# WC_Lower.net
KiCad netlist of a schematic drawn in EAGLE
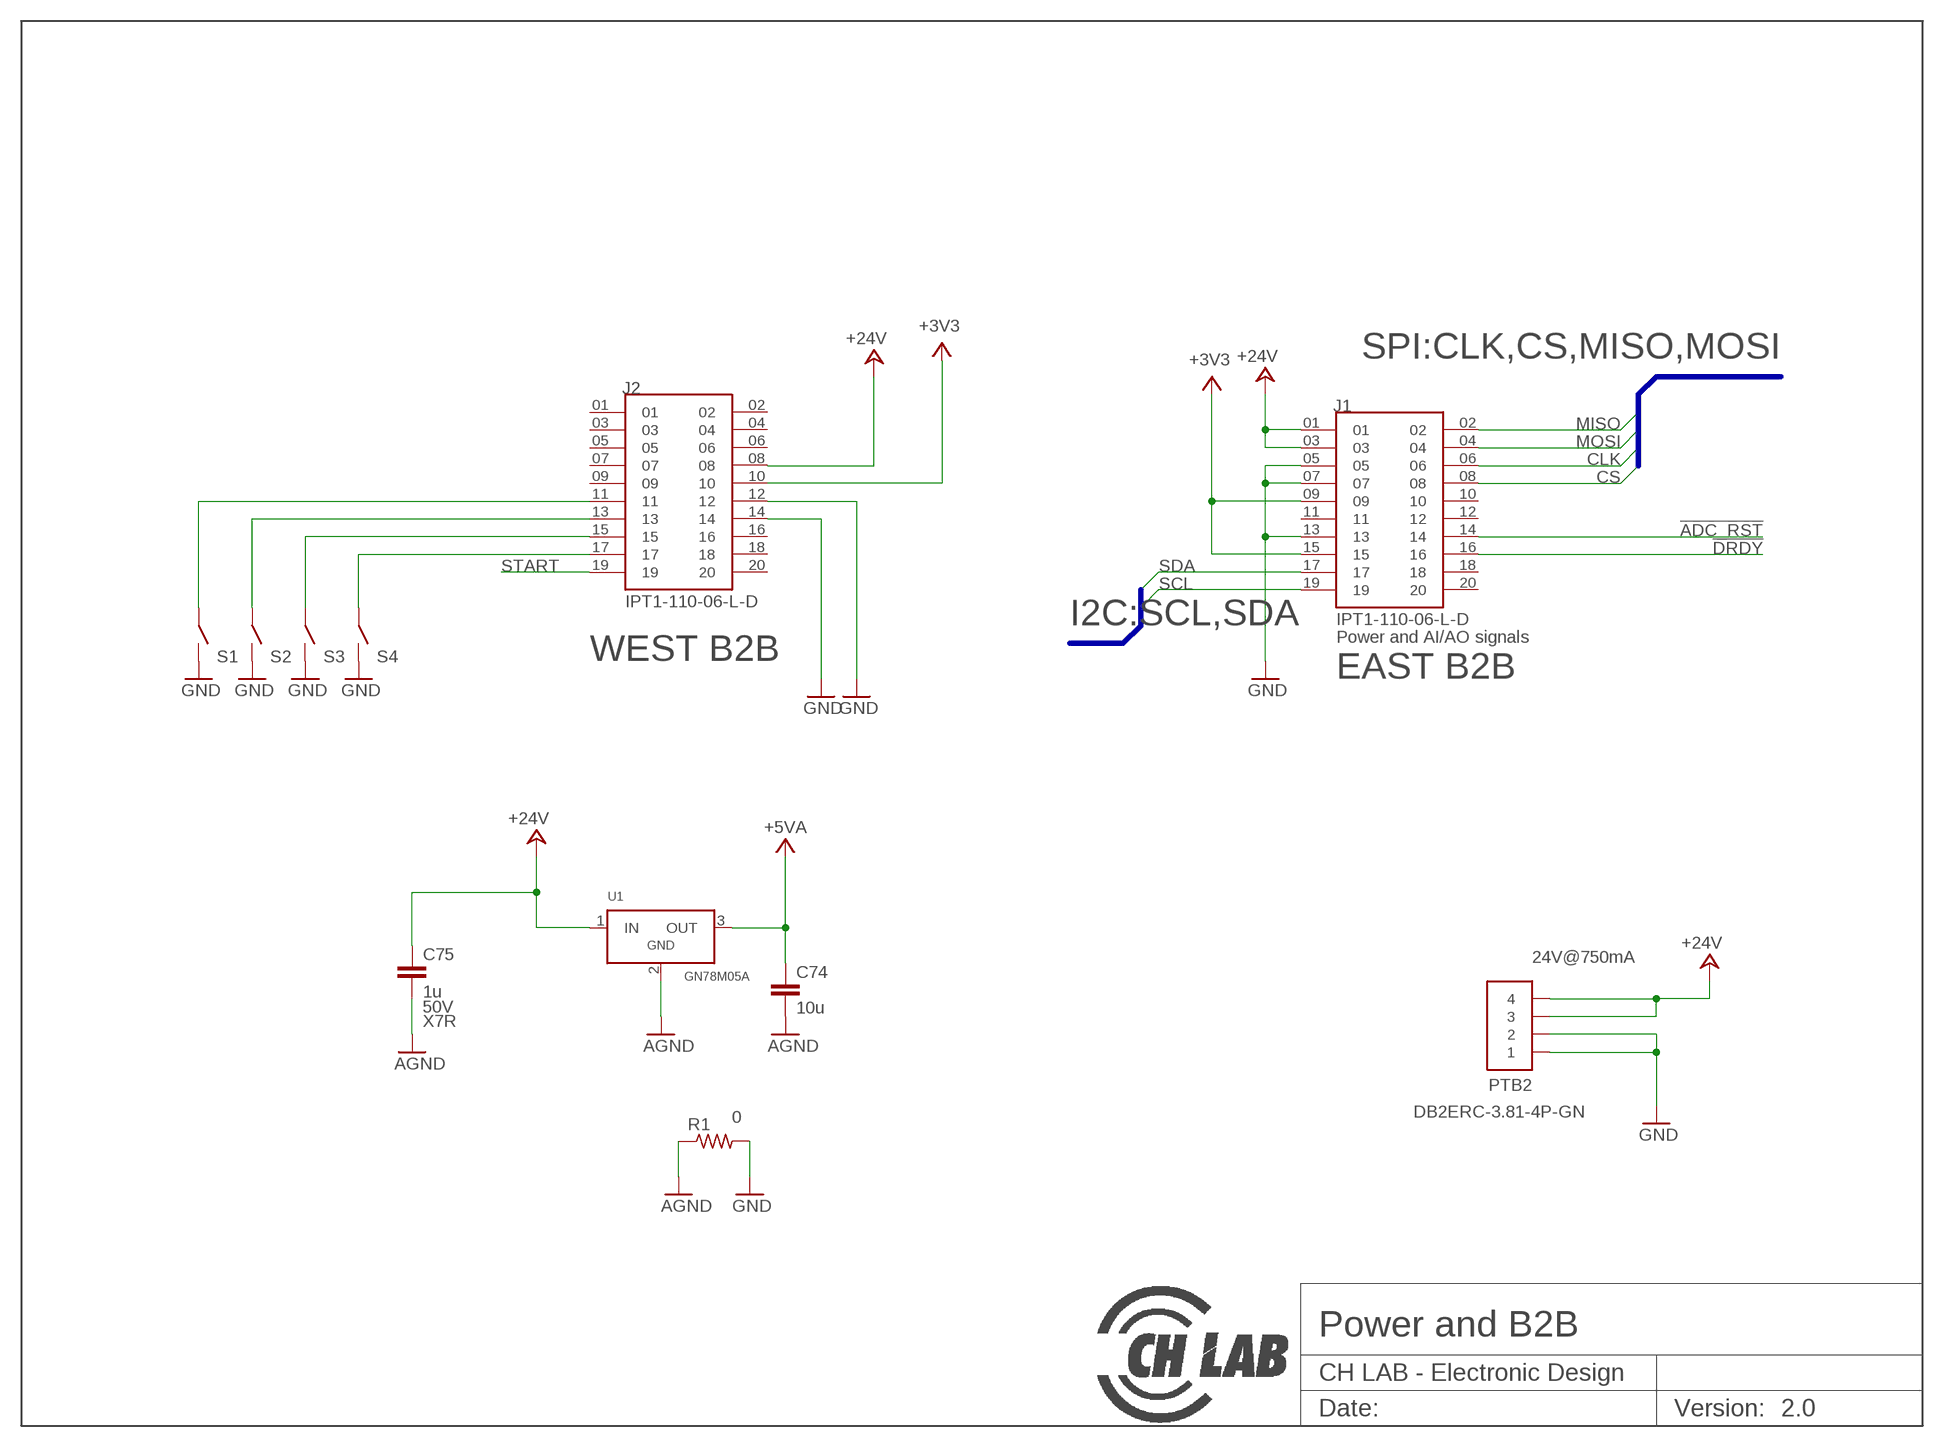
[diagram p0: schematic, sheet 1]
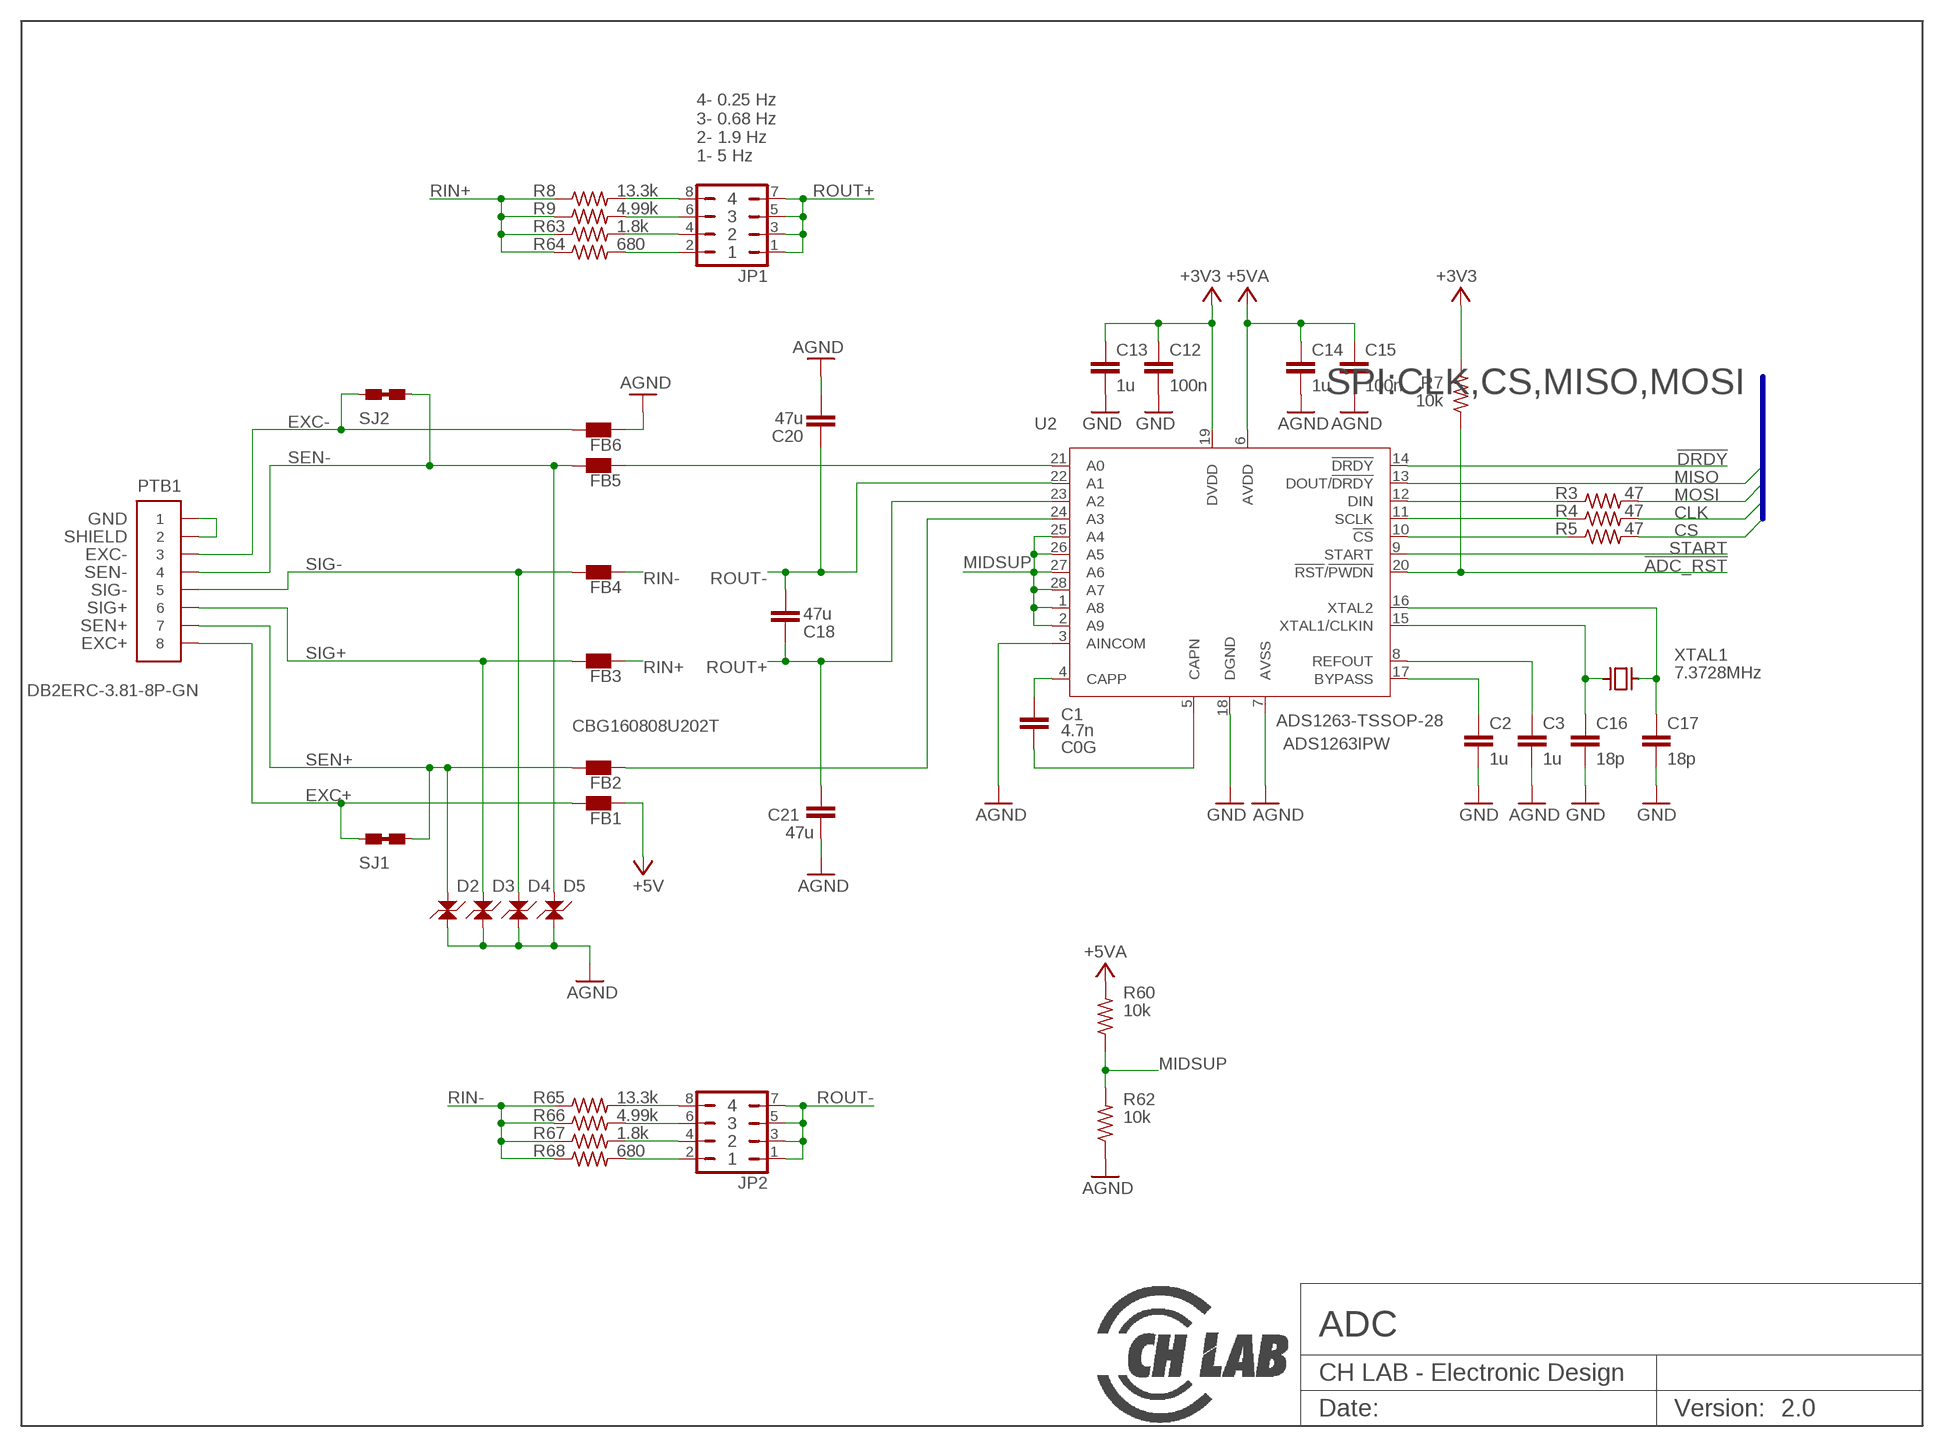
[diagram p1: schematic, sheet 2]

(export (version "E")
  (design (tool "Eeschema 10.0.6"))
  (components
    (comp (ref "C74")
      (value "10u")
      (footprint "eagle-import:C_0805")
      (libsource (lib "eagle-import") (part "C_0805"))
    )
    (comp (ref "C75")
      (value "1u")
      (footprint "eagle-import:C_1206")
      (fields (field (name "D") "X7R") (field (name "ESR") "LOW") (field (name "V") "50V"))
      (libsource (lib "eagle-import") (part "C_1206"))
    )
    (comp (ref "J1")
      (value "IPT1-110-06-L-D")
      (footprint "eagle-import:SAMTEC_IPT1-110-06-L-D")
      (fields (field (name "MANUFACTURER") "Samtec"))
      (libsource (lib "eagle-import") (part "IPT1-110-06-L-D"))
    )
    (comp (ref "J2")
      (value "IPT1-110-06-L-D")
      (footprint "eagle-import:SAMTEC_IPT1-110-06-L-D")
      (fields (field (name "MANUFACTURER") "Samtec"))
      (libsource (lib "eagle-import") (part "IPT1-110-06-L-D"))
    )
    (comp (ref "PTB2")
      (value "DB2ERC-3.81-4P-GN")
      (footprint "eagle-import:1803293")
      (libsource (lib "eagle-import") (part "PLUGTB-4-1803293"))
    )
    (comp (ref "R1")
      (value "0")
      (footprint "eagle-import:R_0603")
      (libsource (lib "eagle-import") (part "R_0603"))
    )
    (comp (ref "S1")
      (value "TSWITCH_SMTR2")
      (footprint "eagle-import:SMTR2")
      (libsource (lib "eagle-import") (part "TSWITCH_SMTR2"))
    )
    (comp (ref "S2")
      (value "TSWITCH_SMTR2")
      (footprint "eagle-import:SMTR2")
      (libsource (lib "eagle-import") (part "TSWITCH_SMTR2"))
    )
    (comp (ref "S3")
      (value "TSWITCH_SMTR2")
      (footprint "eagle-import:SMTR2")
      (libsource (lib "eagle-import") (part "TSWITCH_SMTR2"))
    )
    (comp (ref "S4")
      (value "TSWITCH_SMTR2")
      (footprint "eagle-import:SMTR2")
      (libsource (lib "eagle-import") (part "TSWITCH_SMTR2"))
    )
    (comp (ref "U1")
      (value "GN78M05A")
      (footprint "eagle-import:TO-252")
      (libsource (lib "eagle-import") (part "GN78M05A"))
    )
    (comp (ref "C1")
      (value "4.7n")
      (footprint "eagle-import:C_0603")
      (fields (field (name "DK") "C0G"))
      (libsource (lib "eagle-import") (part "C_0603"))
    )
    (comp (ref "C2")
      (value "1u")
      (footprint "eagle-import:C_0603")
      (libsource (lib "eagle-import") (part "C_0603"))
    )
    (comp (ref "C3")
      (value "1u")
      (footprint "eagle-import:C_0603")
      (libsource (lib "eagle-import") (part "C_0603"))
    )
    (comp (ref "C12")
      (value "100n")
      (footprint "eagle-import:C_0603")
      (libsource (lib "eagle-import") (part "C_0603"))
    )
    (comp (ref "C13")
      (value "1u")
      (footprint "eagle-import:C_0603")
      (libsource (lib "eagle-import") (part "C_0603"))
    )
    (comp (ref "C14")
      (value "1u")
      (footprint "eagle-import:C_0603")
      (libsource (lib "eagle-import") (part "C_0603"))
    )
    (comp (ref "C15")
      (value "100n")
      (footprint "eagle-import:C_0603")
      (libsource (lib "eagle-import") (part "C_0603"))
    )
    (comp (ref "C16")
      (value "18p")
      (footprint "eagle-import:C_0603")
      (libsource (lib "eagle-import") (part "C_0603"))
    )
    (comp (ref "C17")
      (value "18p")
      (footprint "eagle-import:C_0603")
      (libsource (lib "eagle-import") (part "C_0603"))
    )
    (comp (ref "C18")
      (value "47u")
      (footprint "eagle-import:C_1210")
      (libsource (lib "eagle-import") (part "C_1210"))
    )
    (comp (ref "C20")
      (value "47u")
      (footprint "eagle-import:C_1210")
      (libsource (lib "eagle-import") (part "C_1210"))
    )
    (comp (ref "C21")
      (value "47u")
      (footprint "eagle-import:C_1210")
      (libsource (lib "eagle-import") (part "C_1210"))
    )
    (comp (ref "D2")
      (value "LESD5D5.0CT1G")
      (footprint "eagle-import:SOD523")
      (libsource (lib "eagle-import") (part "LESD5D5.0CT1G"))
    )
    (comp (ref "D3")
      (value "LESD5D5.0CT1G")
      (footprint "eagle-import:SOD523")
      (libsource (lib "eagle-import") (part "LESD5D5.0CT1G"))
    )
    (comp (ref "D4")
      (value "LESD5D5.0CT1G")
      (footprint "eagle-import:SOD523")
      (libsource (lib "eagle-import") (part "LESD5D5.0CT1G"))
    )
    (comp (ref "D5")
      (value "LESD5D5.0CT1G")
      (footprint "eagle-import:SOD523")
      (libsource (lib "eagle-import") (part "LESD5D5.0CT1G"))
    )
    (comp (ref "FB1")
      (value "FB_0603")
      (footprint "eagle-import:R_0603")
      (libsource (lib "eagle-import") (part "FB_0603"))
    )
    (comp (ref "FB2")
      (value "FB_0603")
      (footprint "eagle-import:R_0603")
      (libsource (lib "eagle-import") (part "FB_0603"))
    )
    (comp (ref "FB3")
      (value "FB_0603")
      (footprint "eagle-import:R_0603")
      (libsource (lib "eagle-import") (part "FB_0603"))
    )
    (comp (ref "FB4")
      (value "FB_0603")
      (footprint "eagle-import:R_0603")
      (libsource (lib "eagle-import") (part "FB_0603"))
    )
    (comp (ref "FB5")
      (value "FB_0603")
      (footprint "eagle-import:R_0603")
      (libsource (lib "eagle-import") (part "FB_0603"))
    )
    (comp (ref "FB6")
      (value "FB_0603")
      (footprint "eagle-import:R_0603")
      (libsource (lib "eagle-import") (part "FB_0603"))
    )
    (comp (ref "JP1")
      (value "CONVERT-2X4-2.54MALE")
      (footprint "eagle-import:CONN-VERT-2.54MM-2X4-MALE")
      (libsource (lib "eagle-import") (part "CONVERT-2X4-2.54MALE"))
    )
    (comp (ref "JP2")
      (value "CONVERT-2X4-2.54MALE")
      (footprint "eagle-import:CONN-VERT-2.54MM-2X4-MALE")
      (libsource (lib "eagle-import") (part "CONVERT-2X4-2.54MALE"))
    )
    (comp (ref "PTB1")
      (value "DB2ERC-3.81-8P-GN")
      (footprint "eagle-import:1803332")
      (libsource (lib "eagle-import") (part "PLUGTB-8-1803332"))
    )
    (comp (ref "R3")
      (value "47")
      (footprint "eagle-import:R_0402")
      (libsource (lib "eagle-import") (part "R_0402"))
    )
    (comp (ref "R4")
      (value "47")
      (footprint "eagle-import:R_0402")
      (libsource (lib "eagle-import") (part "R_0402"))
    )
    (comp (ref "R5")
      (value "47")
      (footprint "eagle-import:R_0402")
      (libsource (lib "eagle-import") (part "R_0402"))
    )
    (comp (ref "R7")
      (value "10k")
      (footprint "eagle-import:R_0603")
      (libsource (lib "eagle-import") (part "R_0603"))
    )
    (comp (ref "R8")
      (value "13.3k")
      (footprint "eagle-import:R_0603")
      (libsource (lib "eagle-import") (part "R_0603"))
    )
    (comp (ref "R9")
      (value "4.99k")
      (footprint "eagle-import:R_0603")
      (libsource (lib "eagle-import") (part "R_0603"))
    )
    (comp (ref "R60")
      (value "10k")
      (footprint "eagle-import:R_0603")
      (libsource (lib "eagle-import") (part "R_0603"))
    )
    (comp (ref "R62")
      (value "10k")
      (footprint "eagle-import:R_0603")
      (libsource (lib "eagle-import") (part "R_0603"))
    )
    (comp (ref "R63")
      (value "1.8k")
      (footprint "eagle-import:R_0603")
      (libsource (lib "eagle-import") (part "R_0603"))
    )
    (comp (ref "R64")
      (value "680")
      (footprint "eagle-import:R_0603")
      (libsource (lib "eagle-import") (part "R_0603"))
    )
    (comp (ref "R65")
      (value "13.3k")
      (footprint "eagle-import:R_0603")
      (libsource (lib "eagle-import") (part "R_0603"))
    )
    (comp (ref "R66")
      (value "4.99k")
      (footprint "eagle-import:R_0603")
      (libsource (lib "eagle-import") (part "R_0603"))
    )
    (comp (ref "R67")
      (value "1.8k")
      (footprint "eagle-import:R_0603")
      (libsource (lib "eagle-import") (part "R_0603"))
    )
    (comp (ref "R68")
      (value "680")
      (footprint "eagle-import:R_0603")
      (libsource (lib "eagle-import") (part "R_0603"))
    )
    (comp (ref "SJ1")
      (value "SJUMPER-NC")
      (footprint "eagle-import:SJ1")
      (libsource (lib "eagle-import") (part "SJUMPER-NC"))
    )
    (comp (ref "SJ2")
      (value "SJUMPER-NC")
      (footprint "eagle-import:SJ1")
      (libsource (lib "eagle-import") (part "SJUMPER-NC"))
    )
    (comp (ref "U2")
      (value "ADS1263-TSSOP-28")
      (footprint "eagle-import:SOP65P640X120-28N")
      (fields (field (name "MPN") "ADS1263IPW"))
      (libsource (lib "eagle-import") (part "ADS1263-TSSOP-28"))
    )
    (comp (ref "XTAL1")
      (value "7.3728MHz")
      (footprint "eagle-import:XTAL")
      (fields
        (field (name "LINK") "https://www.mouser.com/ProductDetail/ABRACON/ABLS-7.3728MHZ-K4T?qs=uDmhV2jwPReaiEAs5bxjfg%3D%3D")
        (field (name "MPN") "ABLS-7.3728MHZ-K4T")
      )
      (libsource (lib "eagle-import") (part "XTAL_11.4X4.7"))
    )
  )
  (nets
    (net (code "4") (name "+3V3") (class "Default")
      (node (ref "C12") (pin "P$1") (pinfunction "1_P$1") (pintype "passive"))
      (node (ref "C13") (pin "P$1") (pinfunction "1_P$1") (pintype "passive"))
      (node (ref "J1") (pin "09") (pinfunction "09_09") (pintype "passive"))
      (node (ref "J1") (pin "15") (pinfunction "15_15") (pintype "passive"))
      (node (ref "J2") (pin "10") (pinfunction "10_10") (pintype "passive"))
      (node (ref "R7") (pin "2") (pinfunction "2_2") (pintype "passive"))
      (node (ref "U2") (pin "19") (pinfunction "DVDD_19") (pintype "power_in"))
    )
    (net (code "5") (name "+5V") (class "Default")
      (node (ref "FB1") (pin "2") (pinfunction "2_2") (pintype "passive"))
    )
    (net (code "6") (name "+5VA") (class "Default")
      (node (ref "C14") (pin "P$1") (pinfunction "1_P$1") (pintype "passive"))
      (node (ref "C15") (pin "P$1") (pinfunction "1_P$1") (pintype "passive"))
      (node (ref "C74") (pin "P$1") (pinfunction "1_P$1") (pintype "passive"))
      (node (ref "R60") (pin "2") (pinfunction "2_2") (pintype "passive"))
      (node (ref "U1") (pin "3") (pinfunction "OUT_3") (pintype "power_in"))
      (node (ref "U2") (pin "6") (pinfunction "AVDD_6") (pintype "power_in"))
    )
    (net (code "7") (name "+24V") (class "Default")
      (node (ref "C75") (pin "P$1") (pinfunction "1_P$1") (pintype "passive"))
      (node (ref "J1") (pin "01") (pinfunction "01_01") (pintype "passive"))
      (node (ref "J1") (pin "03") (pinfunction "03_03") (pintype "passive"))
      (node (ref "J2") (pin "08") (pinfunction "08_08") (pintype "passive"))
      (node (ref "PTB2") (pin "P$3") (pinfunction "3_P$3") (pintype "bidirectional"))
      (node (ref "PTB2") (pin "P$4") (pinfunction "4_P$4") (pintype "bidirectional"))
      (node (ref "U1") (pin "1") (pinfunction "IN_1") (pintype "power_in"))
    )
    (net (code "11") (name "AGND") (class "Default")
      (node (ref "C14") (pin "P$2") (pinfunction "2_P$2") (pintype "passive"))
      (node (ref "C15") (pin "P$2") (pinfunction "2_P$2") (pintype "passive"))
      (node (ref "C20") (pin "P$1") (pinfunction "1_P$1") (pintype "passive"))
      (node (ref "C21") (pin "P$1") (pinfunction "1_P$1") (pintype "passive"))
      (node (ref "C3") (pin "P$2") (pinfunction "2_P$2") (pintype "passive"))
      (node (ref "C74") (pin "P$2") (pinfunction "2_P$2") (pintype "passive"))
      (node (ref "C75") (pin "P$2") (pinfunction "2_P$2") (pintype "passive"))
      (node (ref "D2") (pin "C") (pinfunction "P$2_C") (pintype "bidirectional"))
      (node (ref "D3") (pin "C") (pinfunction "P$2_C") (pintype "bidirectional"))
      (node (ref "D4") (pin "C") (pinfunction "P$2_C") (pintype "bidirectional"))
      (node (ref "D5") (pin "C") (pinfunction "P$2_C") (pintype "bidirectional"))
      (node (ref "FB6") (pin "2") (pinfunction "2_2") (pintype "passive"))
      (node (ref "R1") (pin "1") (pinfunction "1_1") (pintype "passive"))
      (node (ref "R62") (pin "1") (pinfunction "1_1") (pintype "passive"))
      (node (ref "U1") (pin "2") (pinfunction "GND_2") (pintype "power_in"))
      (node (ref "U2") (pin "3") (pinfunction "AINCOM_3") (pintype "bidirectional"))
      (node (ref "U2") (pin "7") (pinfunction "AVSS_7") (pintype "power_in"))
    )
    (net (code "12") (name "CLK") (class "Default")
      (node (ref "J1") (pin "06") (pinfunction "06_06") (pintype "passive"))
      (node (ref "R4") (pin "2") (pinfunction "2_2") (pintype "passive"))
    )
    (net (code "13") (name "CS") (class "Default")
      (node (ref "J1") (pin "08") (pinfunction "08_08") (pintype "passive"))
      (node (ref "R5") (pin "2") (pinfunction "2_2") (pintype "passive"))
    )
    (net (code "14") (name "EXC+") (class "Default")
      (node (ref "FB1") (pin "1") (pinfunction "1_1") (pintype "passive"))
      (node (ref "PTB1") (pin "P$8") (pinfunction "8_P$8") (pintype "bidirectional"))
      (node (ref "SJ1") (pin "P$1") (pinfunction "P$1_P$1") (pintype "bidirectional"))
    )
    (net (code "15") (name "EXC-") (class "Default")
      (node (ref "FB6") (pin "1") (pinfunction "1_1") (pintype "passive"))
      (node (ref "PTB1") (pin "P$3") (pinfunction "3_P$3") (pintype "bidirectional"))
      (node (ref "SJ2") (pin "P$1") (pinfunction "P$1_P$1") (pintype "bidirectional"))
    )
    (net (code "16") (name "GND") (class "Default")
      (node (ref "C12") (pin "P$2") (pinfunction "2_P$2") (pintype "passive"))
      (node (ref "C13") (pin "P$2") (pinfunction "2_P$2") (pintype "passive"))
      (node (ref "C16") (pin "P$2") (pinfunction "2_P$2") (pintype "passive"))
      (node (ref "C17") (pin "P$2") (pinfunction "2_P$2") (pintype "passive"))
      (node (ref "C2") (pin "P$2") (pinfunction "2_P$2") (pintype "passive"))
      (node (ref "J1") (pin "05") (pinfunction "05_05") (pintype "passive"))
      (node (ref "J1") (pin "07") (pinfunction "07_07") (pintype "passive"))
      (node (ref "J1") (pin "13") (pinfunction "13_13") (pintype "passive"))
      (node (ref "J2") (pin "12") (pinfunction "12_12") (pintype "passive"))
      (node (ref "J2") (pin "14") (pinfunction "14_14") (pintype "passive"))
      (node (ref "PTB2") (pin "P$1") (pinfunction "1_P$1") (pintype "bidirectional"))
      (node (ref "PTB2") (pin "P$2") (pinfunction "2_P$2") (pintype "bidirectional"))
      (node (ref "R1") (pin "2") (pinfunction "2_2") (pintype "passive"))
      (node (ref "S1") (pin "P$3") (pinfunction "P$2_P$3") (pintype "bidirectional"))
      (node (ref "S1") (pin "P$4") (pinfunction "P$2_P$4") (pintype "bidirectional"))
      (node (ref "S2") (pin "P$3") (pinfunction "P$2_P$3") (pintype "bidirectional"))
      (node (ref "S2") (pin "P$4") (pinfunction "P$2_P$4") (pintype "bidirectional"))
      (node (ref "S3") (pin "P$3") (pinfunction "P$2_P$3") (pintype "bidirectional"))
      (node (ref "S3") (pin "P$4") (pinfunction "P$2_P$4") (pintype "bidirectional"))
      (node (ref "S4") (pin "P$3") (pinfunction "P$2_P$3") (pintype "bidirectional"))
      (node (ref "S4") (pin "P$4") (pinfunction "P$2_P$4") (pintype "bidirectional"))
      (node (ref "U2") (pin "18") (pinfunction "DGND_18") (pintype "power_in"))
    )
    (net (code "17") (name "MIDSUP") (class "Default")
      (node (ref "R60") (pin "1") (pinfunction "1_1") (pintype "passive"))
      (node (ref "R62") (pin "2") (pinfunction "2_2") (pintype "passive"))
      (node (ref "U2") (pin "1") (pinfunction "A8_1") (pintype "bidirectional"))
      (node (ref "U2") (pin "2") (pinfunction "A9_2") (pintype "bidirectional"))
      (node (ref "U2") (pin "25") (pinfunction "A4_25") (pintype "bidirectional"))
      (node (ref "U2") (pin "26") (pinfunction "A5_26") (pintype "bidirectional"))
      (node (ref "U2") (pin "27") (pinfunction "A6_27") (pintype "bidirectional"))
      (node (ref "U2") (pin "28") (pinfunction "A7_28") (pintype "bidirectional"))
    )
    (net (code "18") (name "MISO") (class "Default")
      (node (ref "J1") (pin "02") (pinfunction "02_02") (pintype "passive"))
      (node (ref "U2") (pin "13") (pinfunction "DOUT/~{DRDY}_13") (pintype "output"))
    )
    (net (code "19") (name "MOSI") (class "Default")
      (node (ref "J1") (pin "04") (pinfunction "04_04") (pintype "passive"))
      (node (ref "R3") (pin "2") (pinfunction "2_2") (pintype "passive"))
    )
    (net (code "20") (name "Net-(C1-1)") (class "Default")
      (node (ref "C1") (pin "P$1") (pinfunction "1_P$1") (pintype "passive"))
      (node (ref "U2") (pin "4") (pinfunction "CAPP_4") (pintype "output"))
    )
    (net (code "21") (name "Net-(C1-2)") (class "Default")
      (node (ref "C1") (pin "P$2") (pinfunction "2_P$2") (pintype "passive"))
      (node (ref "U2") (pin "5") (pinfunction "CAPN_5") (pintype "output"))
    )
    (net (code "22") (name "Net-(C2-1)") (class "Default")
      (node (ref "C2") (pin "P$1") (pinfunction "1_P$1") (pintype "passive"))
      (node (ref "U2") (pin "17") (pinfunction "BYPASS_17") (pintype "output"))
    )
    (net (code "23") (name "Net-(C3-1)") (class "Default")
      (node (ref "C3") (pin "P$1") (pinfunction "1_P$1") (pintype "passive"))
      (node (ref "U2") (pin "8") (pinfunction "REFOUT_8") (pintype "output"))
    )
    (net (code "24") (name "Net-(C16-1)") (class "Default")
      (node (ref "C16") (pin "P$1") (pinfunction "1_P$1") (pintype "passive"))
      (node (ref "U2") (pin "15") (pinfunction "XTAL1/CLKIN_15") (pintype "input"))
      (node (ref "XTAL1") (pin "1") (pinfunction "X1_1") (pintype "passive"))
    )
    (net (code "25") (name "Net-(C17-1)") (class "Default")
      (node (ref "C17") (pin "P$1") (pinfunction "1_P$1") (pintype "passive"))
      (node (ref "U2") (pin "16") (pinfunction "XTAL2_16") (pintype "input"))
      (node (ref "XTAL1") (pin "2") (pinfunction "X2_2") (pintype "passive"))
    )
    (net (code "26") (name "Net-(J2-Pad11)") (class "Default")
      (node (ref "J2") (pin "11") (pinfunction "11_11") (pintype "passive"))
      (node (ref "S1") (pin "P$1") (pinfunction "P$1_P$1") (pintype "bidirectional"))
      (node (ref "S1") (pin "P$2") (pinfunction "P$1_P$2") (pintype "bidirectional"))
    )
    (net (code "27") (name "Net-(J2-Pad13)") (class "Default")
      (node (ref "J2") (pin "13") (pinfunction "13_13") (pintype "passive"))
      (node (ref "S2") (pin "P$1") (pinfunction "P$1_P$1") (pintype "bidirectional"))
      (node (ref "S2") (pin "P$2") (pinfunction "P$1_P$2") (pintype "bidirectional"))
    )
    (net (code "28") (name "Net-(J2-Pad15)") (class "Default")
      (node (ref "J2") (pin "15") (pinfunction "15_15") (pintype "passive"))
      (node (ref "S3") (pin "P$1") (pinfunction "P$1_P$1") (pintype "bidirectional"))
      (node (ref "S3") (pin "P$2") (pinfunction "P$1_P$2") (pintype "bidirectional"))
    )
    (net (code "29") (name "Net-(J2-Pad17)") (class "Default")
      (node (ref "J2") (pin "17") (pinfunction "17_17") (pintype "passive"))
      (node (ref "S4") (pin "P$1") (pinfunction "P$1_P$1") (pintype "bidirectional"))
      (node (ref "S4") (pin "P$2") (pinfunction "P$1_P$2") (pintype "bidirectional"))
    )
    (net (code "30") (name "Net-(JP1-Pad2)") (class "Default")
      (node (ref "JP1") (pin "2") (pinfunction "2_2") (pintype "passive"))
      (node (ref "R64") (pin "2") (pinfunction "2_2") (pintype "passive"))
    )
    (net (code "31") (name "Net-(JP1-Pad4)") (class "Default")
      (node (ref "JP1") (pin "4") (pinfunction "4_4") (pintype "passive"))
      (node (ref "R63") (pin "2") (pinfunction "2_2") (pintype "passive"))
    )
    (net (code "32") (name "Net-(JP1-Pad6)") (class "Default")
      (node (ref "JP1") (pin "6") (pinfunction "6_6") (pintype "passive"))
      (node (ref "R9") (pin "2") (pinfunction "2_2") (pintype "passive"))
    )
    (net (code "33") (name "Net-(JP1-Pad8)") (class "Default")
      (node (ref "JP1") (pin "8") (pinfunction "8_8") (pintype "passive"))
      (node (ref "R8") (pin "2") (pinfunction "2_2") (pintype "passive"))
    )
    (net (code "34") (name "Net-(JP2-Pad2)") (class "Default")
      (node (ref "JP2") (pin "2") (pinfunction "2_2") (pintype "passive"))
      (node (ref "R68") (pin "2") (pinfunction "2_2") (pintype "passive"))
    )
    (net (code "35") (name "Net-(JP2-Pad4)") (class "Default")
      (node (ref "JP2") (pin "4") (pinfunction "4_4") (pintype "passive"))
      (node (ref "R67") (pin "2") (pinfunction "2_2") (pintype "passive"))
    )
    (net (code "36") (name "Net-(JP2-Pad6)") (class "Default")
      (node (ref "JP2") (pin "6") (pinfunction "6_6") (pintype "passive"))
      (node (ref "R66") (pin "2") (pinfunction "2_2") (pintype "passive"))
    )
    (net (code "37") (name "Net-(JP2-Pad8)") (class "Default")
      (node (ref "JP2") (pin "8") (pinfunction "8_8") (pintype "passive"))
      (node (ref "R65") (pin "2") (pinfunction "2_2") (pintype "passive"))
    )
    (net (code "38") (name "Net-(PTB1-1)") (class "Default")
      (node (ref "PTB1") (pin "P$1") (pinfunction "1_P$1") (pintype "bidirectional"))
      (node (ref "PTB1") (pin "P$2") (pinfunction "2_P$2") (pintype "bidirectional"))
    )
    (net (code "39") (name "Net-(U2-A0)") (class "Default")
      (node (ref "FB5") (pin "2") (pinfunction "2_2") (pintype "passive"))
      (node (ref "U2") (pin "21") (pinfunction "A0_21") (pintype "bidirectional"))
    )
    (net (code "40") (name "Net-(U2-A3)") (class "Default")
      (node (ref "FB2") (pin "2") (pinfunction "2_2") (pintype "passive"))
      (node (ref "U2") (pin "24") (pinfunction "A3_24") (pintype "bidirectional"))
    )
    (net (code "41") (name "Net-(U2-DIN)") (class "Default")
      (node (ref "R3") (pin "1") (pinfunction "1_1") (pintype "passive"))
      (node (ref "U2") (pin "12") (pinfunction "DIN_12") (pintype "input"))
    )
    (net (code "42") (name "Net-(U2-SCLK)") (class "Default")
      (node (ref "R4") (pin "1") (pinfunction "1_1") (pintype "passive"))
      (node (ref "U2") (pin "11") (pinfunction "SCLK_11") (pintype "input"))
    )
    (net (code "43") (name "Net-(U2-~{CS})") (class "Default")
      (node (ref "R5") (pin "1") (pinfunction "1_1") (pintype "passive"))
      (node (ref "U2") (pin "10") (pinfunction "~{CS}_10") (pintype "input"))
    )
    (net (code "44") (name "RIN+") (class "Default")
      (node (ref "FB3") (pin "2") (pinfunction "2_2") (pintype "passive"))
      (node (ref "R63") (pin "1") (pinfunction "1_1") (pintype "passive"))
      (node (ref "R64") (pin "1") (pinfunction "1_1") (pintype "passive"))
      (node (ref "R8") (pin "1") (pinfunction "1_1") (pintype "passive"))
      (node (ref "R9") (pin "1") (pinfunction "1_1") (pintype "passive"))
    )
    (net (code "45") (name "RIN-") (class "Default")
      (node (ref "FB4") (pin "2") (pinfunction "2_2") (pintype "passive"))
      (node (ref "R65") (pin "1") (pinfunction "1_1") (pintype "passive"))
      (node (ref "R66") (pin "1") (pinfunction "1_1") (pintype "passive"))
      (node (ref "R67") (pin "1") (pinfunction "1_1") (pintype "passive"))
      (node (ref "R68") (pin "1") (pinfunction "1_1") (pintype "passive"))
    )
    (net (code "46") (name "ROUT+") (class "Default")
      (node (ref "C18") (pin "P$1") (pinfunction "1_P$1") (pintype "passive"))
      (node (ref "C21") (pin "P$2") (pinfunction "2_P$2") (pintype "passive"))
      (node (ref "JP1") (pin "1") (pinfunction "1_1") (pintype "passive"))
      (node (ref "JP1") (pin "3") (pinfunction "3_3") (pintype "passive"))
      (node (ref "JP1") (pin "5") (pinfunction "5_5") (pintype "passive"))
      (node (ref "JP1") (pin "7") (pinfunction "7_7") (pintype "passive"))
      (node (ref "U2") (pin "23") (pinfunction "A2_23") (pintype "bidirectional"))
    )
    (net (code "47") (name "ROUT-") (class "Default")
      (node (ref "C18") (pin "P$2") (pinfunction "2_P$2") (pintype "passive"))
      (node (ref "C20") (pin "P$2") (pinfunction "2_P$2") (pintype "passive"))
      (node (ref "JP2") (pin "1") (pinfunction "1_1") (pintype "passive"))
      (node (ref "JP2") (pin "3") (pinfunction "3_3") (pintype "passive"))
      (node (ref "JP2") (pin "5") (pinfunction "5_5") (pintype "passive"))
      (node (ref "JP2") (pin "7") (pinfunction "7_7") (pintype "passive"))
      (node (ref "U2") (pin "22") (pinfunction "A1_22") (pintype "bidirectional"))
    )
    (net (code "48") (name "SCL") (class "Default")
      (node (ref "J1") (pin "19") (pinfunction "19_19") (pintype "passive"))
    )
    (net (code "49") (name "SDA") (class "Default")
      (node (ref "J1") (pin "17") (pinfunction "17_17") (pintype "passive"))
    )
    (net (code "50") (name "SEN+") (class "Default")
      (node (ref "D2") (pin "A") (pinfunction "P$1_A") (pintype "bidirectional"))
      (node (ref "FB2") (pin "1") (pinfunction "1_1") (pintype "passive"))
      (node (ref "PTB1") (pin "P$7") (pinfunction "7_P$7") (pintype "bidirectional"))
      (node (ref "SJ1") (pin "P$2") (pinfunction "P$2_P$2") (pintype "bidirectional"))
    )
    (net (code "51") (name "SEN-") (class "Default")
      (node (ref "D5") (pin "A") (pinfunction "P$1_A") (pintype "bidirectional"))
      (node (ref "FB5") (pin "1") (pinfunction "1_1") (pintype "passive"))
      (node (ref "PTB1") (pin "P$4") (pinfunction "4_P$4") (pintype "bidirectional"))
      (node (ref "SJ2") (pin "P$2") (pinfunction "P$2_P$2") (pintype "bidirectional"))
    )
    (net (code "52") (name "SIG+") (class "Default")
      (node (ref "D3") (pin "A") (pinfunction "P$1_A") (pintype "bidirectional"))
      (node (ref "FB3") (pin "1") (pinfunction "1_1") (pintype "passive"))
      (node (ref "PTB1") (pin "P$6") (pinfunction "6_P$6") (pintype "bidirectional"))
    )
    (net (code "53") (name "SIG-") (class "Default")
      (node (ref "D4") (pin "A") (pinfunction "P$1_A") (pintype "bidirectional"))
      (node (ref "FB4") (pin "1") (pinfunction "1_1") (pintype "passive"))
      (node (ref "PTB1") (pin "P$5") (pinfunction "5_P$5") (pintype "bidirectional"))
    )
    (net (code "54") (name "START") (class "Default")
      (node (ref "J2") (pin "19") (pinfunction "19_19") (pintype "passive"))
      (node (ref "U2") (pin "9") (pinfunction "START_9") (pintype "input"))
    )
    (net (code "55") (name "unconnected-(J1-Pad10)") (class "Default")
      (node (ref "J1") (pin "10") (pinfunction "10_10") (pintype "passive"))
    )
    (net (code "56") (name "unconnected-(J1-Pad11)") (class "Default")
      (node (ref "J1") (pin "11") (pinfunction "11_11") (pintype "passive"))
    )
    (net (code "57") (name "unconnected-(J1-Pad12)") (class "Default")
      (node (ref "J1") (pin "12") (pinfunction "12_12") (pintype "passive"))
    )
    (net (code "58") (name "unconnected-(J1-Pad18)") (class "Default")
      (node (ref "J1") (pin "18") (pinfunction "18_18") (pintype "passive"))
    )
    (net (code "59") (name "unconnected-(J1-Pad20)") (class "Default")
      (node (ref "J1") (pin "20") (pinfunction "20_20") (pintype "passive"))
    )
    (net (code "60") (name "unconnected-(J2-Pad01)") (class "Default")
      (node (ref "J2") (pin "01") (pinfunction "01_01") (pintype "passive"))
    )
    (net (code "61") (name "unconnected-(J2-Pad02)") (class "Default")
      (node (ref "J2") (pin "02") (pinfunction "02_02") (pintype "passive"))
    )
    (net (code "62") (name "unconnected-(J2-Pad03)") (class "Default")
      (node (ref "J2") (pin "03") (pinfunction "03_03") (pintype "passive"))
    )
    (net (code "63") (name "unconnected-(J2-Pad04)") (class "Default")
      (node (ref "J2") (pin "04") (pinfunction "04_04") (pintype "passive"))
    )
    (net (code "64") (name "unconnected-(J2-Pad05)") (class "Default")
      (node (ref "J2") (pin "05") (pinfunction "05_05") (pintype "passive"))
    )
    (net (code "65") (name "unconnected-(J2-Pad06)") (class "Default")
      (node (ref "J2") (pin "06") (pinfunction "06_06") (pintype "passive"))
    )
    (net (code "66") (name "unconnected-(J2-Pad07)") (class "Default")
      (node (ref "J2") (pin "07") (pinfunction "07_07") (pintype "passive"))
    )
    (net (code "67") (name "unconnected-(J2-Pad09)") (class "Default")
      (node (ref "J2") (pin "09") (pinfunction "09_09") (pintype "passive"))
    )
    (net (code "68") (name "unconnected-(J2-Pad16)") (class "Default")
      (node (ref "J2") (pin "16") (pinfunction "16_16") (pintype "passive"))
    )
    (net (code "69") (name "unconnected-(J2-Pad18)") (class "Default")
      (node (ref "J2") (pin "18") (pinfunction "18_18") (pintype "passive"))
    )
    (net (code "70") (name "unconnected-(J2-Pad20)") (class "Default")
      (node (ref "J2") (pin "20") (pinfunction "20_20") (pintype "passive"))
    )
    (net (code "71") (name "~{ADC_RST}") (class "Default")
      (node (ref "J1") (pin "14") (pinfunction "14_14") (pintype "passive"))
      (node (ref "R7") (pin "1") (pinfunction "1_1") (pintype "passive"))
      (node (ref "U2") (pin "20") (pinfunction "~{RST}/~{PWDN}_20") (pintype "input"))
    )
    (net (code "72") (name "~{DRDY}") (class "Default")
      (node (ref "J1") (pin "16") (pinfunction "16_16") (pintype "passive"))
      (node (ref "U2") (pin "14") (pinfunction "~{DRDY}_14") (pintype "output"))
    )
  )
)
